# openSX70_ALADDIN_V39_20180124.net
KiCad netlist of a schematic drawn in EAGLE
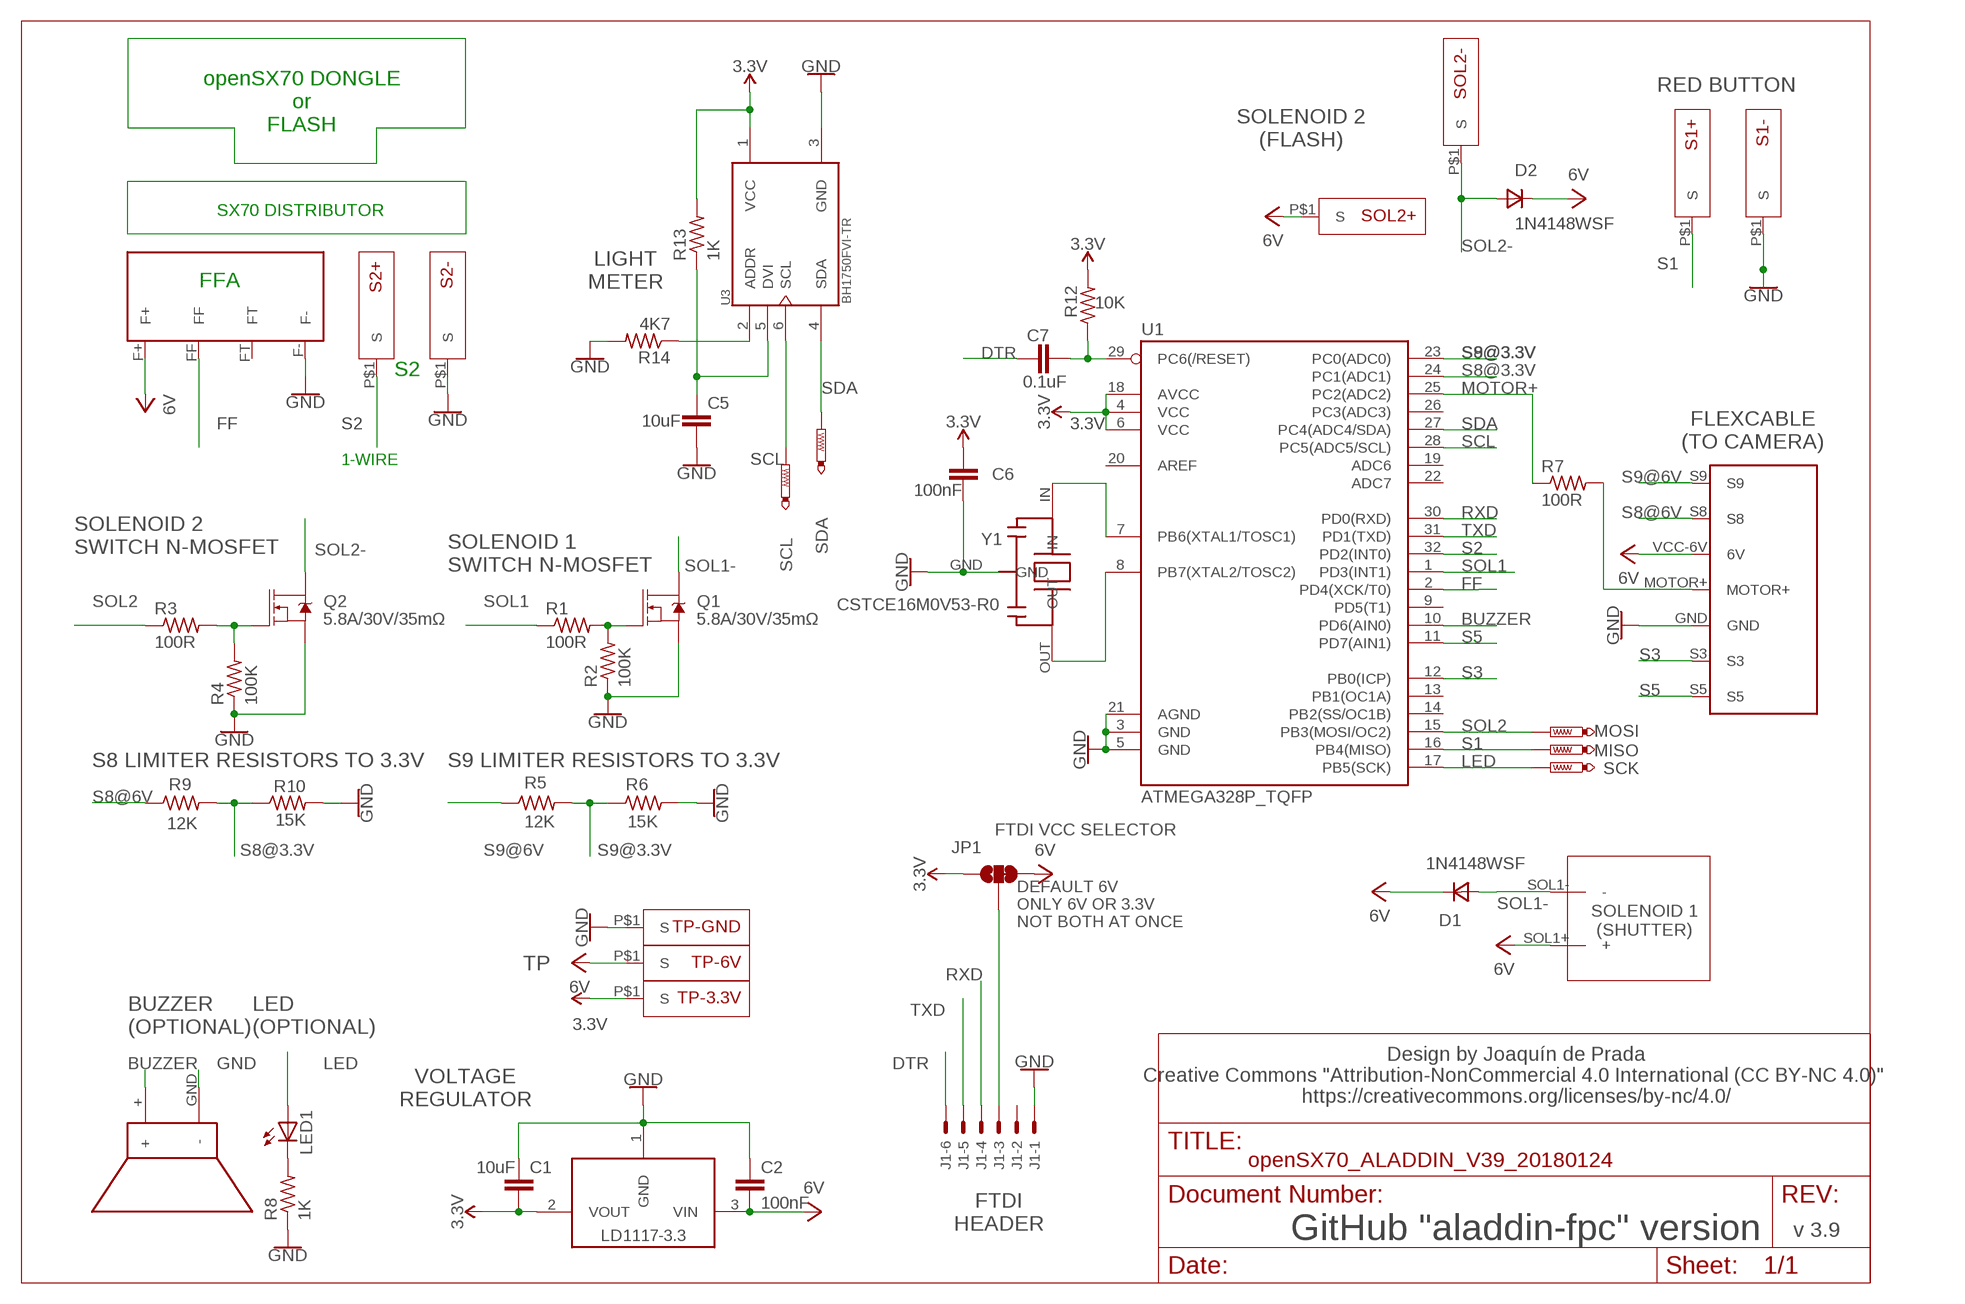
[diagram p0: schematic, sheet 1]

(export (version "E")
  (design (tool "Eeschema 10.0.6"))
  (components
    (comp (ref "BUZZ1")
      (value "CSET8-5G")
      (footprint "eagle-import:CSET8-5G_PACKAGE")
      (libsource (lib "eagle-import") (part "CSET8-5G"))
    )
    (comp (ref "C1")
      (value "10uF")
      (footprint "eagle-import:0603")
      (libsource (lib "eagle-import") (part "10UF-0603-6.3V-20%"))
    )
    (comp (ref "C2")
      (value "100nF")
      (footprint "eagle-import:C0603K")
      (libsource (lib "eagle-import") (part "C-EUC0603K"))
    )
    (comp (ref "C5")
      (value "10uF")
      (footprint "eagle-import:0603")
      (libsource (lib "eagle-import") (part "10UF-0603-6.3V-20%"))
    )
    (comp (ref "C6")
      (value "100nF")
      (footprint "eagle-import:C0603")
      (libsource (lib "eagle-import") (part "C-EUC0603"))
    )
    (comp (ref "C7")
      (value "0.1uF")
      (footprint "eagle-import:0603")
      (libsource (lib "eagle-import") (part "0.1UF-0603-25V-(+80/-20%)"))
    )
    (comp (ref "D1")
      (value "1N4148WSF")
      (footprint "eagle-import:SOD323")
      (fields (field (name "MPN") "CDSOD323-T05C"))
      (libsource (lib "eagle-import") (part "DSOD323"))
    )
    (comp (ref "D2")
      (value "1N4148WSF")
      (footprint "eagle-import:SOD323")
      (fields (field (name "MPN") "CDSOD323-T05C"))
      (libsource (lib "eagle-import") (part "DSOD323"))
    )
    (comp (ref "J1")
      (value "GND")
      (footprint "eagle-import:XF2L-0625-1")
      (fields (field (name "MF") "OMRON COMPONENTS USA") (field (name "MPN") "XF2L-0625-1"))
      (libsource (lib "eagle-import") (part "XF2-06?25-1L"))
    )
    (comp (ref "JP1")
      (value "FTDI VCC SELECTOR")
      (footprint "eagle-import:SMT-JUMPER_3_1-NC_TRACE_SILK")
      (libsource (lib "eagle-import") (part "JUMPER-SMT_3_1-NC_TRACE_SILK"))
    )
    (comp (ref "LD11173.3V")
      (value "LD1117 3.3V")
      (footprint "eagle-import:SOT223")
      (fields (field (name "MF") "Advanced Monolithic Systems") (field (name "MP") "AMS1117-5.0"))
      (libsource (lib "eagle-import") (part "LD1117-3.3"))
    )
    (comp (ref "LED1")
      (value "LEDCHIPLED_0805")
      (footprint "eagle-import:CHIPLED_0805")
      (libsource (lib "eagle-import") (part "LEDCHIPLED_0805"))
    )
    (comp (ref "MISO")
      (value "PTR1TP08R")
      (footprint "eagle-import:TP08R")
      (libsource (lib "eagle-import") (part "PTR1TP08R"))
    )
    (comp (ref "MOSI")
      (value "PTR1TP08R")
      (footprint "eagle-import:TP08R")
      (libsource (lib "eagle-import") (part "PTR1TP08R"))
    )
    (comp (ref "Q1")
      (value "5.8A/30V/35mΩ")
      (footprint "eagle-import:SOT23-3")
      (libsource (lib "eagle-import") (part "MOSFET-NCH-AO3404A"))
    )
    (comp (ref "Q2")
      (value "5.8A/30V/35mΩ")
      (footprint "eagle-import:SOT23-3")
      (libsource (lib "eagle-import") (part "MOSFET-NCH-AO3404A"))
    )
    (comp (ref "R1")
      (value "100R")
      (footprint "eagle-import:R0603")
      (libsource (lib "eagle-import") (part "R-US_R0603"))
    )
    (comp (ref "R2")
      (value "100K")
      (footprint "eagle-import:R0603")
      (libsource (lib "eagle-import") (part "R-US_R0603"))
    )
    (comp (ref "R3")
      (value "100R")
      (footprint "eagle-import:R0603")
      (libsource (lib "eagle-import") (part "R-US_R0603"))
    )
    (comp (ref "R4")
      (value "100K")
      (footprint "eagle-import:R0603")
      (libsource (lib "eagle-import") (part "R-US_R0603"))
    )
    (comp (ref "R5")
      (value "12K")
      (footprint "eagle-import:R0603")
      (libsource (lib "eagle-import") (part "R-US_R0603"))
    )
    (comp (ref "R6")
      (value "15K")
      (footprint "eagle-import:R0603")
      (libsource (lib "eagle-import") (part "R-US_R0603"))
    )
    (comp (ref "R7")
      (value "100R")
      (footprint "eagle-import:R0603")
      (libsource (lib "eagle-import") (part "R-US_R0603"))
    )
    (comp (ref "R8")
      (value "1K")
      (footprint "eagle-import:R0603")
      (libsource (lib "eagle-import") (part "R-US_R0603"))
    )
    (comp (ref "R9")
      (value "12K")
      (footprint "eagle-import:R0603")
      (libsource (lib "eagle-import") (part "R-US_R0603"))
    )
    (comp (ref "R10")
      (value "15K")
      (footprint "eagle-import:R0603")
      (libsource (lib "eagle-import") (part "R-US_R0603"))
    )
    (comp (ref "R12")
      (value "10K")
      (footprint "eagle-import:R0603")
      (libsource (lib "eagle-import") (part "R-US_R0603"))
    )
    (comp (ref "R13")
      (value "1K")
      (footprint "eagle-import:R0603")
      (libsource (lib "eagle-import") (part "R-US_R0603"))
    )
    (comp (ref "R14")
      (value "4K7")
      (footprint "eagle-import:R0603")
      (libsource (lib "eagle-import") (part "R-US_R0603"))
    )
    (comp (ref "S1+")
      (value "SX70-S-PAD-NEW")
      (footprint "eagle-import:SX70-S-PAD2")
      (libsource (lib "eagle-import") (part "SX70-S-PAD-NEW"))
    )
    (comp (ref "S1-")
      (value "SX70-S-PAD-NEW")
      (footprint "eagle-import:SX70-S-PAD2")
      (libsource (lib "eagle-import") (part "SX70-S-PAD-NEW"))
    )
    (comp (ref "S2+")
      (value "SX70-S-PAD-NEW")
      (footprint "eagle-import:SX70-S-PAD2")
      (libsource (lib "eagle-import") (part "SX70-S-PAD-NEW"))
    )
    (comp (ref "S2-")
      (value "SX70-S-PAD-NEW")
      (footprint "eagle-import:SX70-S-PAD2")
      (libsource (lib "eagle-import") (part "SX70-S-PAD-NEW"))
    )
    (comp (ref "SCK")
      (value "PTR1TP08R")
      (footprint "eagle-import:TP08R")
      (libsource (lib "eagle-import") (part "PTR1TP08R"))
    )
    (comp (ref "SCL")
      (value "PTR1TP08R")
      (footprint "eagle-import:TP08R")
      (libsource (lib "eagle-import") (part "PTR1TP08R"))
    )
    (comp (ref "SDA")
      (value "PTR1TP08R")
      (footprint "eagle-import:TP08R")
      (libsource (lib "eagle-import") (part "PTR1TP08R"))
    )
    (comp (ref "SOL1")
      (value "SX70-SOLENOID1-2PADS")
      (footprint "eagle-import:SX70-SOLENOID1-2")
      (libsource (lib "eagle-import") (part "SX70-SOLENOID1-2PADS"))
    )
    (comp (ref "SOL2+")
      (value "SX70-S-PAD-NEW")
      (footprint "eagle-import:SX70-S-PAD2")
      (libsource (lib "eagle-import") (part "SX70-S-PAD-NEW"))
    )
    (comp (ref "SOL2-")
      (value "SX70-S-PAD-NEW")
      (footprint "eagle-import:SX70-S-PAD2")
      (libsource (lib "eagle-import") (part "SX70-S-PAD-NEW"))
    )
    (comp (ref "TP-3.3V")
      (value "SX70-S-PAD-NEW")
      (footprint "eagle-import:SX70-S-PAD2")
      (libsource (lib "eagle-import") (part "SX70-S-PAD-NEW"))
    )
    (comp (ref "TP-6V")
      (value "SX70-S-PAD-NEW")
      (footprint "eagle-import:SX70-S-PAD2")
      (libsource (lib "eagle-import") (part "SX70-S-PAD-NEW"))
    )
    (comp (ref "TP-GND")
      (value "SX70-S-PAD-NEW")
      (footprint "eagle-import:SX70-S-PAD2")
      (libsource (lib "eagle-import") (part "SX70-S-PAD-NEW"))
    )
    (comp (ref "U$1")
      (value "SX70-7-PAD")
      (footprint "eagle-import:SX70-7-PAD")
      (libsource (lib "eagle-import") (part "SX70-7-PAD"))
    )
    (comp (ref "U$2")
      (value "FFA")
      (footprint "eagle-import:FFA-PAD-PACKAGE")
      (libsource (lib "eagle-import") (part "SX70-FFA-PAD"))
    )
    (comp (ref "U1")
      (value "ATMEGA328P_TQFP")
      (footprint "eagle-import:TQFP32-08")
      (libsource (lib "eagle-import") (part "ATMEGA328P_TQFP"))
    )
    (comp (ref "U3")
      (value "BH1750FVI-TR")
      (footprint "eagle-import:SOTFL50P300X75-6N")
      (fields (field (name "MF") "Rohm"))
      (libsource (lib "eagle-import") (part "BH1750FVI-TR"))
    )
    (comp (ref "Y1")
      (value "CSTCE16M0V53-R0")
      (footprint "eagle-import:CFP95P160X100-3N")
      (fields (field (name "MF") "Murata"))
      (libsource (lib "eagle-import") (part "CSTCE16M0V53-R0"))
    )
  )
  (nets
    (net (code "1") (name "/BUZZER") (class "Default")
      (node (ref "BUZZ1") (pin "+") (pinfunction "+_+") (pintype "bidirectional"))
      (node (ref "U1") (pin "10") (pinfunction "PD6(AIN0)_10") (pintype "bidirectional"))
    )
    (net (code "2") (name "/DTR") (class "Default")
      (node (ref "C7") (pin "1") (pinfunction "1_1") (pintype "passive"))
      (node (ref "J1") (pin "6") (pinfunction "MS_6") (pintype "passive"))
    )
    (net (code "3") (name "/FF") (class "Default")
      (node (ref "U$2") (pin "FF") (pinfunction "FF_FF") (pintype "bidirectional"))
      (node (ref "U1") (pin "2") (pinfunction "PD4(XCK/T0)_2") (pintype "bidirectional"))
    )
    (net (code "4") (name "/LED") (class "Default")
      (node (ref "LED1") (pin "A") (pinfunction "A_A") (pintype "passive"))
      (node (ref "SCK") (pin "TP") (pinfunction "TP_TP") (pintype "input"))
      (node (ref "U1") (pin "17") (pinfunction "PB5(SCK)_17") (pintype "bidirectional"))
    )
    (net (code "5") (name "/MOTOR+") (class "Default")
      (node (ref "R7") (pin "1") (pinfunction "1_1") (pintype "passive"))
      (node (ref "U1") (pin "25") (pinfunction "PC2(ADC2)_25") (pintype "bidirectional"))
    )
    (net (code "6") (name "/RXD") (class "Default")
      (node (ref "J1") (pin "4") (pinfunction "MS_4") (pintype "passive"))
      (node (ref "U1") (pin "30") (pinfunction "PD0(RXD)_30") (pintype "bidirectional"))
    )
    (net (code "7") (name "/S1") (class "Default")
      (node (ref "MISO") (pin "TP") (pinfunction "TP_TP") (pintype "input"))
      (node (ref "S1+") (pin "P$1") (pinfunction "S_P$1") (pintype "bidirectional"))
      (node (ref "U1") (pin "16") (pinfunction "PB4(MISO)_16") (pintype "bidirectional"))
    )
    (net (code "8") (name "/S2") (class "Default")
      (node (ref "S2+") (pin "P$1") (pinfunction "S_P$1") (pintype "bidirectional"))
      (node (ref "U1") (pin "32") (pinfunction "PD2(INT0)_32") (pintype "bidirectional"))
    )
    (net (code "9") (name "/S3") (class "Default")
      (node (ref "U$1") (pin "S3") (pinfunction "S3_S3") (pintype "bidirectional"))
      (node (ref "U1") (pin "12") (pinfunction "PB0(ICP)_12") (pintype "bidirectional"))
    )
    (net (code "10") (name "/S5") (class "Default")
      (node (ref "U$1") (pin "S5") (pinfunction "S5_S5") (pintype "bidirectional"))
      (node (ref "U1") (pin "11") (pinfunction "PD7(AIN1)_11") (pintype "bidirectional"))
    )
    (net (code "11") (name "/S8@3.3V") (class "Default")
      (node (ref "R10") (pin "1") (pinfunction "1_1") (pintype "passive"))
      (node (ref "R9") (pin "2") (pinfunction "2_2") (pintype "passive"))
      (node (ref "U1") (pin "24") (pinfunction "PC1(ADC1)_24") (pintype "bidirectional"))
    )
    (net (code "12") (name "/S8@6V") (class "Default")
      (node (ref "R9") (pin "1") (pinfunction "1_1") (pintype "passive"))
      (node (ref "U$1") (pin "S8") (pinfunction "S8_S8") (pintype "bidirectional"))
    )
    (net (code "13") (name "/S9@3.3V") (class "Default")
      (node (ref "R5") (pin "2") (pinfunction "2_2") (pintype "passive"))
      (node (ref "R6") (pin "1") (pinfunction "1_1") (pintype "passive"))
      (node (ref "U1") (pin "23") (pinfunction "PC0(ADC0)_23") (pintype "bidirectional"))
    )
    (net (code "14") (name "/S9@6V") (class "Default")
      (node (ref "R5") (pin "1") (pinfunction "1_1") (pintype "passive"))
      (node (ref "U$1") (pin "S9") (pinfunction "S9_S9") (pintype "bidirectional"))
    )
    (net (code "15") (name "/SCL") (class "Default")
      (node (ref "SCL") (pin "TP") (pinfunction "TP_TP") (pintype "input"))
      (node (ref "U1") (pin "28") (pinfunction "PC5(ADC5/SCL)_28") (pintype "bidirectional"))
      (node (ref "U3") (pin "6") (pinfunction "SCL_6") (pintype "input"))
    )
    (net (code "16") (name "/SDA") (class "Default")
      (node (ref "SDA") (pin "TP") (pinfunction "TP_TP") (pintype "input"))
      (node (ref "U1") (pin "27") (pinfunction "PC4(ADC4/SDA)_27") (pintype "bidirectional"))
      (node (ref "U3") (pin "4") (pinfunction "SDA_4") (pintype "bidirectional"))
    )
    (net (code "17") (name "/SOL1") (class "Default")
      (node (ref "R1") (pin "1") (pinfunction "1_1") (pintype "passive"))
      (node (ref "U1") (pin "1") (pinfunction "PD3(INT1)_1") (pintype "bidirectional"))
    )
    (net (code "18") (name "/SOL1-") (class "Default")
      (node (ref "D1") (pin "2") (pinfunction "A_2") (pintype "passive"))
      (node (ref "Q1") (pin "3") (pinfunction "D_3") (pintype "bidirectional"))
      (node (ref "SOL1") (pin "SOL1-") (pinfunction "-_SOL1-") (pintype "bidirectional"))
    )
    (net (code "19") (name "/SOL2") (class "Default")
      (node (ref "MOSI") (pin "TP") (pinfunction "TP_TP") (pintype "input"))
      (node (ref "R3") (pin "1") (pinfunction "1_1") (pintype "passive"))
      (node (ref "U1") (pin "15") (pinfunction "PB3(MOSI/OC2)_15") (pintype "bidirectional"))
    )
    (net (code "20") (name "/SOL2-") (class "Default")
      (node (ref "D2") (pin "2") (pinfunction "A_2") (pintype "passive"))
      (node (ref "Q2") (pin "3") (pinfunction "D_3") (pintype "bidirectional"))
      (node (ref "SOL2-") (pin "P$1") (pinfunction "S_P$1") (pintype "bidirectional"))
    )
    (net (code "21") (name "/TXD") (class "Default")
      (node (ref "J1") (pin "5") (pinfunction "MS_5") (pintype "passive"))
      (node (ref "U1") (pin "31") (pinfunction "PD1(TXD)_31") (pintype "bidirectional"))
    )
    (net (code "22") (name "3.3V") (class "Default")
      (node (ref "C1") (pin "2") (pinfunction "2_2") (pintype "passive"))
      (node (ref "C6") (pin "1") (pinfunction "1_1") (pintype "passive"))
      (node (ref "JP1") (pin "1") (pinfunction "1_1") (pintype "passive"))
      (node (ref "LD11173.3V") (pin "2") (pinfunction "VOUT_2") (pintype "bidirectional"))
      (node (ref "R12") (pin "2") (pinfunction "2_2") (pintype "passive"))
      (node (ref "R13") (pin "2") (pinfunction "2_2") (pintype "passive"))
      (node (ref "TP-3.3V") (pin "P$1") (pinfunction "S_P$1") (pintype "bidirectional"))
      (node (ref "U1") (pin "18") (pinfunction "AVCC_18") (pintype "bidirectional"))
      (node (ref "U1") (pin "4") (pinfunction "VCC_4") (pintype "bidirectional"))
      (node (ref "U1") (pin "6") (pinfunction "VCC_6") (pintype "bidirectional"))
      (node (ref "U3") (pin "1") (pinfunction "VCC_1") (pintype "power_in"))
    )
    (net (code "23") (name "6V") (class "Default")
      (node (ref "C2") (pin "2") (pinfunction "2_2") (pintype "passive"))
      (node (ref "D1") (pin "1") (pinfunction "C_1") (pintype "passive"))
      (node (ref "D2") (pin "1") (pinfunction "C_1") (pintype "passive"))
      (node (ref "JP1") (pin "3") (pinfunction "3_3") (pintype "passive"))
      (node (ref "LD11173.3V") (pin "3") (pinfunction "VIN_3") (pintype "bidirectional"))
      (node (ref "SOL1") (pin "SOL1+") (pinfunction "+_SOL1+") (pintype "bidirectional"))
      (node (ref "SOL2+") (pin "P$1") (pinfunction "S_P$1") (pintype "bidirectional"))
      (node (ref "TP-6V") (pin "P$1") (pinfunction "S_P$1") (pintype "bidirectional"))
      (node (ref "U$1") (pin "VCC-6V") (pinfunction "6V_VCC-6V") (pintype "bidirectional"))
      (node (ref "U$2") (pin "F+") (pinfunction "F+_F+") (pintype "bidirectional"))
    )
    (net (code "24") (name "GND") (class "Default")
      (node (ref "BUZZ1") (pin "GND") (pinfunction "-_GND") (pintype "bidirectional"))
      (node (ref "C1") (pin "1") (pinfunction "1_1") (pintype "passive"))
      (node (ref "C2") (pin "1") (pinfunction "1_1") (pintype "passive"))
      (node (ref "C5") (pin "2") (pinfunction "2_2") (pintype "passive"))
      (node (ref "C6") (pin "2") (pinfunction "2_2") (pintype "passive"))
      (node (ref "J1") (pin "1") (pinfunction "MS_1") (pintype "passive"))
      (node (ref "LD11173.3V") (pin "1") (pinfunction "GND_1") (pintype "bidirectional"))
      (node (ref "Q1") (pin "2") (pinfunction "S_2") (pintype "bidirectional"))
      (node (ref "Q2") (pin "2") (pinfunction "S_2") (pintype "bidirectional"))
      (node (ref "R10") (pin "2") (pinfunction "2_2") (pintype "passive"))
      (node (ref "R14") (pin "2") (pinfunction "2_2") (pintype "passive"))
      (node (ref "R2") (pin "1") (pinfunction "1_1") (pintype "passive"))
      (node (ref "R4") (pin "1") (pinfunction "1_1") (pintype "passive"))
      (node (ref "R6") (pin "2") (pinfunction "2_2") (pintype "passive"))
      (node (ref "R8") (pin "1") (pinfunction "1_1") (pintype "passive"))
      (node (ref "S1-") (pin "P$1") (pinfunction "S_P$1") (pintype "bidirectional"))
      (node (ref "S2-") (pin "P$1") (pinfunction "S_P$1") (pintype "bidirectional"))
      (node (ref "TP-GND") (pin "P$1") (pinfunction "S_P$1") (pintype "bidirectional"))
      (node (ref "U$1") (pin "GND") (pinfunction "GND_GND") (pintype "bidirectional"))
      (node (ref "U$2") (pin "F-") (pinfunction "F-_F-") (pintype "bidirectional"))
      (node (ref "U1") (pin "21") (pinfunction "AGND_21") (pintype "bidirectional"))
      (node (ref "U1") (pin "3") (pinfunction "GND_3") (pintype "bidirectional"))
      (node (ref "U1") (pin "5") (pinfunction "GND_5") (pintype "bidirectional"))
      (node (ref "U3") (pin "3") (pinfunction "GND_3") (pintype "power_in"))
      (node (ref "Y1") (pin "GND") (pinfunction "GND_GND") (pintype "passive"))
    )
    (net (code "25") (name "Net-(J1C-MS)") (class "Default")
      (node (ref "J1") (pin "3") (pinfunction "MS_3") (pintype "passive"))
      (node (ref "JP1") (pin "2") (pinfunction "2_2") (pintype "passive"))
    )
    (net (code "26") (name "Net-(LED1-PadC)") (class "Default")
      (node (ref "LED1") (pin "C") (pinfunction "C_C") (pintype "passive"))
      (node (ref "R8") (pin "2") (pinfunction "2_2") (pintype "passive"))
    )
    (net (code "27") (name "Net-(Q1-G)") (class "Default")
      (node (ref "Q1") (pin "1") (pinfunction "G_1") (pintype "bidirectional"))
      (node (ref "R1") (pin "2") (pinfunction "2_2") (pintype "passive"))
      (node (ref "R2") (pin "2") (pinfunction "2_2") (pintype "passive"))
    )
    (net (code "28") (name "Net-(Q2-G)") (class "Default")
      (node (ref "Q2") (pin "1") (pinfunction "G_1") (pintype "bidirectional"))
      (node (ref "R3") (pin "2") (pinfunction "2_2") (pintype "passive"))
      (node (ref "R4") (pin "2") (pinfunction "2_2") (pintype "passive"))
    )
    (net (code "29") (name "Net-(R7-Pad2)") (class "Default")
      (node (ref "R7") (pin "2") (pinfunction "2_2") (pintype "passive"))
      (node (ref "U$1") (pin "MOTOR+") (pinfunction "MOTOR+_MOTOR+") (pintype "bidirectional"))
    )
    (net (code "30") (name "Net-(U1-PB6(XTAL1{slash}TOSC1))") (class "Default")
      (node (ref "U1") (pin "7") (pinfunction "PB6(XTAL1/TOSC1)_7") (pintype "bidirectional"))
      (node (ref "Y1") (pin "IN") (pinfunction "IN_IN") (pintype "input"))
    )
    (net (code "31") (name "Net-(U1-PB7(XTAL2{slash}TOSC2))") (class "Default")
      (node (ref "U1") (pin "8") (pinfunction "PB7(XTAL2/TOSC2)_8") (pintype "bidirectional"))
      (node (ref "Y1") (pin "OUT") (pinfunction "OUT_OUT") (pintype "output"))
    )
    (net (code "32") (name "Net-(U1-PC6({slash}RESET))") (class "Default")
      (node (ref "C7") (pin "2") (pinfunction "2_2") (pintype "passive"))
      (node (ref "R12") (pin "1") (pinfunction "1_1") (pintype "passive"))
      (node (ref "U1") (pin "29") (pinfunction "PC6(/RESET)_29") (pintype "bidirectional"))
    )
    (net (code "33") (name "Net-(U3-ADDR)") (class "Default")
      (node (ref "R14") (pin "1") (pinfunction "1_1") (pintype "passive"))
      (node (ref "U3") (pin "2") (pinfunction "ADDR_2") (pintype "input"))
    )
    (net (code "34") (name "Net-(U3-DVI)") (class "Default")
      (node (ref "C5") (pin "1") (pinfunction "1_1") (pintype "passive"))
      (node (ref "R13") (pin "1") (pinfunction "1_1") (pintype "passive"))
      (node (ref "U3") (pin "5") (pinfunction "DVI_5") (pintype "input"))
    )
    (net (code "35") (name "unconnected-(J1B-MS-Pad2)") (class "Default")
      (node (ref "J1") (pin "2") (pinfunction "MS_2") (pintype "passive"))
    )
    (net (code "36") (name "unconnected-(U$2-PadFT)") (class "Default")
      (node (ref "U$2") (pin "FT") (pinfunction "FT_FT") (pintype "bidirectional"))
    )
    (net (code "37") (name "unconnected-(U1-ADC6-Pad19)") (class "Default")
      (node (ref "U1") (pin "19") (pinfunction "ADC6_19") (pintype "bidirectional"))
    )
    (net (code "38") (name "unconnected-(U1-ADC7-Pad22)") (class "Default")
      (node (ref "U1") (pin "22") (pinfunction "ADC7_22") (pintype "bidirectional"))
    )
    (net (code "39") (name "unconnected-(U1-AREF-Pad20)") (class "Default")
      (node (ref "U1") (pin "20") (pinfunction "AREF_20") (pintype "bidirectional"))
    )
    (net (code "40") (name "unconnected-(U1-PB1(OC1A)-Pad13)") (class "Default")
      (node (ref "U1") (pin "13") (pinfunction "PB1(OC1A)_13") (pintype "bidirectional"))
    )
    (net (code "41") (name "unconnected-(U1-PB2(SS{slash}OC1B)-Pad14)") (class "Default")
      (node (ref "U1") (pin "14") (pinfunction "PB2(SS/OC1B)_14") (pintype "bidirectional"))
    )
    (net (code "42") (name "unconnected-(U1-PC3(ADC3)-Pad26)") (class "Default")
      (node (ref "U1") (pin "26") (pinfunction "PC3(ADC3)_26") (pintype "bidirectional"))
    )
    (net (code "43") (name "unconnected-(U1-PD5(T1)-Pad9)") (class "Default")
      (node (ref "U1") (pin "9") (pinfunction "PD5(T1)_9") (pintype "bidirectional"))
    )
  )
)
